# Sheet1_MCU2_0.net
KiCad netlist of a schematic drawn in Altium Designer
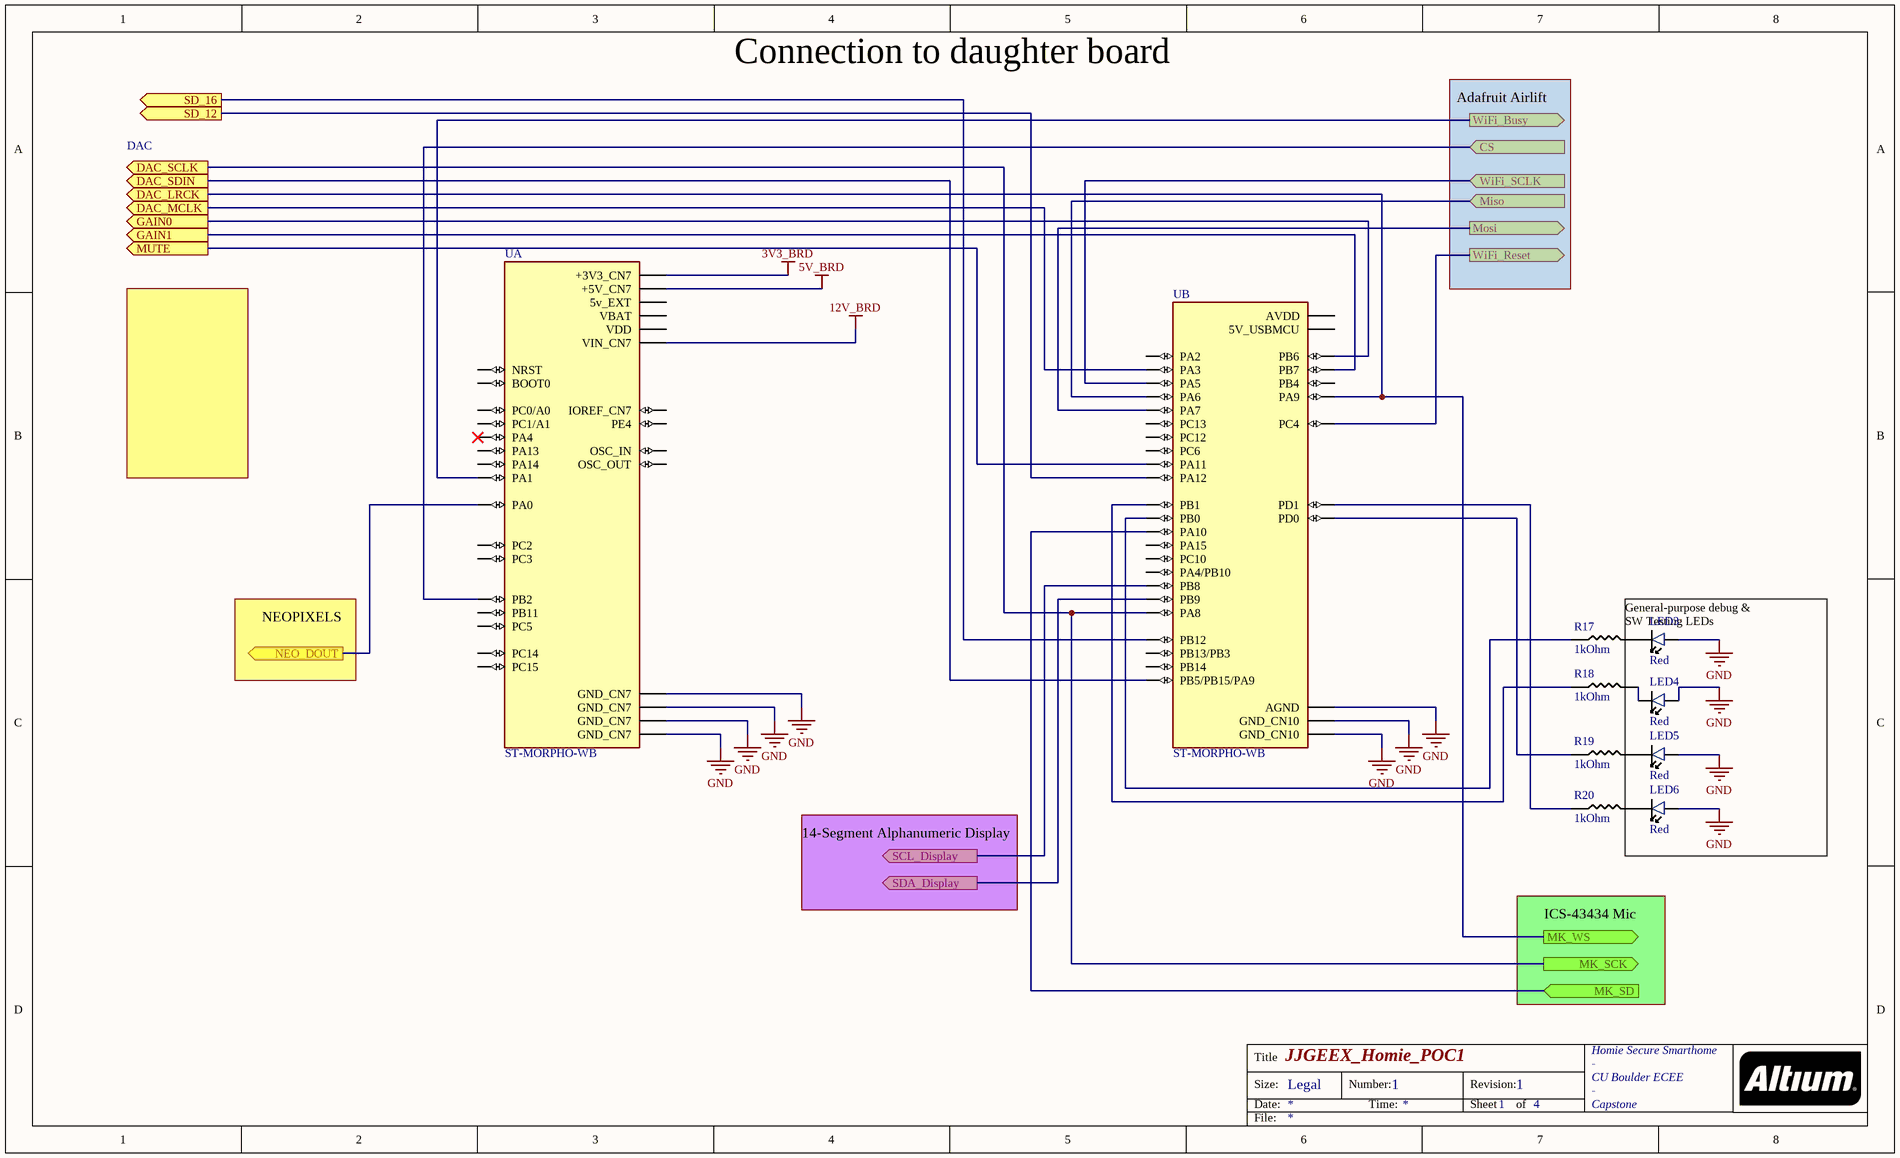
[diagram p0: Sheet1_MCU2.0.SchDoc]

(export (version "E")
  (design (tool "Eeschema 10.0.6"))
  (components
    (comp (ref "LED3")
      (value "Red")
      (footprint "LED0603-R-RD")
      (description "LIGHT EMITTING DIODES (LED) RED 520~625NM 90~100MCD@20MA TOP VIEW 0603 ROHS")
      (fields (field (name "MFR") "Hubei KENTO Elec") (field (name "Comment") "KT-0603R"))
      (libsource (lib "Homie_IntegratedLibraryV2") (part "LED_RED_0603"))
    )
    (comp (ref "LED4")
      (value "Red")
      (footprint "LED0603-R-RD")
      (description "LIGHT EMITTING DIODES (LED) RED 520~625NM 90~100MCD@20MA TOP VIEW 0603 ROHS")
      (fields (field (name "MFR") "Hubei KENTO Elec") (field (name "Comment") "KT-0603R"))
      (libsource (lib "Homie_IntegratedLibraryV2") (part "LED_RED_0603"))
    )
    (comp (ref "LED5")
      (value "Red")
      (footprint "LED0603-R-RD")
      (description "LIGHT EMITTING DIODES (LED) RED 520~625NM 90~100MCD@20MA TOP VIEW 0603 ROHS")
      (fields (field (name "MFR") "Hubei KENTO Elec") (field (name "Comment") "KT-0603R"))
      (libsource (lib "Homie_IntegratedLibraryV2") (part "LED_RED_0603"))
    )
    (comp (ref "LED6")
      (value "Red")
      (footprint "LED0603-R-RD")
      (description "LIGHT EMITTING DIODES (LED) RED 520~625NM 90~100MCD@20MA TOP VIEW 0603 ROHS")
      (fields (field (name "MFR") "Hubei KENTO Elec") (field (name "Comment") "KT-0603R"))
      (libsource (lib "Homie_IntegratedLibraryV2") (part "LED_RED_0603"))
    )
    (comp (ref "R17")
      (value "1kOhm")
      (footprint "R0603")
      (description "1kOhm +-1%  0603")
      (fields (field (name "MFR") "Uniroyal") (field (name "Comment") "1 kOhm"))
      (libsource (lib "Homie_IntegratedLibraryV2") (part "R_1kOhm_0603"))
    )
    (comp (ref "R18")
      (value "1kOhm")
      (footprint "R0603")
      (description "1kOhm +-1%  0603")
      (fields (field (name "MFR") "Uniroyal") (field (name "Comment") "1 kOhm"))
      (libsource (lib "Homie_IntegratedLibraryV2") (part "R_1kOhm_0603"))
    )
    (comp (ref "R19")
      (value "1kOhm")
      (footprint "R0603")
      (description "1kOhm +-1%  0603")
      (fields (field (name "MFR") "Uniroyal") (field (name "Comment") "1 kOhm"))
      (libsource (lib "Homie_IntegratedLibraryV2") (part "R_1kOhm_0603"))
    )
    (comp (ref "R20")
      (value "1kOhm")
      (footprint "R0603")
      (description "1kOhm +-1%  0603")
      (fields (field (name "MFR") "Uniroyal") (field (name "Comment") "1 kOhm"))
      (libsource (lib "Homie_IntegratedLibraryV2") (part "R_1kOhm_0603"))
    )
    (comp (ref "U")
      (value "ST-MORPHO-WB")
      (footprint "ST-MORPHO-WB")
      (description "P-NUCLEO-WB55 Header Footprint")
      (fields (field (name "MF") "STMicroelectronics") (field (name "MP") "NUCLEO-F030R8"))
      (libsource (lib "Homie_IntegratedLibraryV2") (part "ST-MORPHO-WB"))
    )
  )
  (nets
    (net (code "1") (name "/CS") (class "Default")
      (node (ref "U") (pin "CN7_2") (pinfunction "PB2_CN7_2") (pintype "bidirectional"))
    )
    (net (code "2") (name "/DAC_LRCK") (class "Default")
      (node (ref "U") (pin "CN10_19") (pinfunction "PA9_CN10_19") (pintype "bidirectional"))
    )
    (net (code "3") (name "/DAC_MCLK") (class "Default")
      (node (ref "U") (pin "CN10_37") (pinfunction "PA3_CN10_37") (pintype "bidirectional"))
    )
    (net (code "4") (name "/DAC_SCLK") (class "Default")
      (node (ref "U") (pin "CN10_25") (pinfunction "PA8_CN10_25") (pintype "bidirectional"))
    )
    (net (code "5") (name "/DAC_SDIN") (class "Default")
      (node (ref "U") (pin "CN10_26") (pinfunction "PB5/PB15/PA9_CN10_26") (pintype "bidirectional"))
    )
    (net (code "6") (name "/GAIN0") (class "Default")
      (node (ref "U") (pin "CN10_34") (pinfunction "PB6_CN10_34") (pintype "bidirectional"))
    )
    (net (code "7") (name "/GAIN1") (class "Default")
      (node (ref "U") (pin "CN10_6") (pinfunction "PB7_CN10_6") (pintype "bidirectional"))
    )
    (net (code "8") (name "/MK_SD") (class "Default")
      (node (ref "U") (pin "CN10_31") (pinfunction "PA10_CN10_31") (pintype "bidirectional"))
    )
    (net (code "9") (name "/MUTE") (class "Default")
      (node (ref "U") (pin "CN10_14") (pinfunction "PA11_CN10_14") (pintype "bidirectional"))
    )
    (net (code "10") (name "/Miso") (class "Default")
      (node (ref "U") (pin "CN10_13") (pinfunction "PA6_CN10_13") (pintype "bidirectional"))
    )
    (net (code "11") (name "/Mosi") (class "Default")
      (node (ref "U") (pin "CN10_15") (pinfunction "PA7_CN10_15") (pintype "bidirectional"))
    )
    (net (code "12") (name "/NEO_DOUT") (class "Default")
      (node (ref "U") (pin "CN7_34") (pinfunction "PA0_CN7_34") (pintype "bidirectional"))
    )
    (net (code "13") (name "/SCL_Display") (class "Default")
      (node (ref "U") (pin "CN10_3") (pinfunction "PB8_CN10_3") (pintype "bidirectional"))
    )
    (net (code "14") (name "/SDA_Display") (class "Default")
      (node (ref "U") (pin "CN10_5") (pinfunction "PB9_CN10_5") (pintype "bidirectional"))
    )
    (net (code "15") (name "/SD_12") (class "Default")
      (node (ref "U") (pin "CN10_12") (pinfunction "PA12_CN10_12") (pintype "bidirectional"))
    )
    (net (code "16") (name "/SD_16") (class "Default")
      (node (ref "U") (pin "CN10_16") (pinfunction "PB12_CN10_16") (pintype "bidirectional"))
    )
    (net (code "17") (name "/WiFi_Busy") (class "Default")
      (node (ref "U") (pin "CN7_32") (pinfunction "PA1_CN7_32") (pintype "bidirectional"))
    )
    (net (code "18") (name "/WiFi_Reset") (class "Default")
      (node (ref "U") (pin "CN10_1") (pinfunction "PC4_CN10_1") (pintype "bidirectional"))
    )
    (net (code "19") (name "/WiFi_SCLK") (class "Default")
      (node (ref "U") (pin "CN10_11") (pinfunction "PA5_CN10_11") (pintype "bidirectional"))
    )
    (net (code "20") (name "3V3_BRD") (class "Default")
      (node (ref "U") (pin "CN7_16") (pinfunction "+3V3_CN7_CN7_16") (pintype "power_in"))
    )
    (net (code "21") (name "5V_BRD") (class "Default")
      (node (ref "U") (pin "CN7_18") (pinfunction "+5V_CN7_CN7_18") (pintype "power_in"))
    )
    (net (code "22") (name "12V_BRD") (class "Default")
      (node (ref "U") (pin "CN7_24") (pinfunction "VIN_CN7_CN7_24") (pintype "power_in"))
    )
    (net (code "23") (name "GND") (class "Default")
      (node (ref "LED3") (pin "2") (pinfunction "2_2") (pintype "passive"))
      (node (ref "LED4") (pin "2") (pinfunction "2_2") (pintype "passive"))
      (node (ref "LED5") (pin "2") (pinfunction "2_2") (pintype "passive"))
      (node (ref "LED6") (pin "2") (pinfunction "2_2") (pintype "passive"))
      (node (ref "U") (pin "CN10_20") (pinfunction "GND_CN10_CN10_20") (pintype "power_in"))
      (node (ref "U") (pin "CN10_32") (pinfunction "AGND_CN10_32") (pintype "power_in"))
      (node (ref "U") (pin "CN10_9") (pinfunction "GND_CN10_CN10_9") (pintype "power_in"))
      (node (ref "U") (pin "CN7_19") (pinfunction "GND_CN7_CN7_19") (pintype "power_in"))
      (node (ref "U") (pin "CN7_20") (pinfunction "GND_CN7_CN7_20") (pintype "power_in"))
      (node (ref "U") (pin "CN7_22") (pinfunction "GND_CN7_CN7_22") (pintype "power_in"))
      (node (ref "U") (pin "CN7_8") (pinfunction "GND_CN7_CN7_8") (pintype "power_in"))
    )
    (net (code "24") (name "Net-(LED3-Pad1)") (class "Default")
      (node (ref "LED3") (pin "1") (pinfunction "1_1") (pintype "passive"))
      (node (ref "R17") (pin "2") (pinfunction "2_2") (pintype "passive"))
    )
    (net (code "25") (name "Net-(LED4-Pad1)") (class "Default")
      (node (ref "LED4") (pin "1") (pinfunction "1_1") (pintype "passive"))
      (node (ref "R18") (pin "2") (pinfunction "2_2") (pintype "passive"))
    )
    (net (code "26") (name "Net-(LED5-Pad1)") (class "Default")
      (node (ref "LED5") (pin "1") (pinfunction "1_1") (pintype "passive"))
      (node (ref "R19") (pin "2") (pinfunction "2_2") (pintype "passive"))
    )
    (net (code "27") (name "Net-(LED6-Pad1)") (class "Default")
      (node (ref "LED6") (pin "1") (pinfunction "1_1") (pintype "passive"))
      (node (ref "R20") (pin "2") (pinfunction "2_2") (pintype "passive"))
    )
    (net (code "28") (name "Net-(UB-PB0)") (class "Default")
      (node (ref "R17") (pin "1") (pinfunction "1_1") (pintype "passive"))
      (node (ref "U") (pin "CN10_22") (pinfunction "PB0_CN10_22") (pintype "bidirectional"))
    )
    (net (code "29") (name "Net-(UB-PB1)") (class "Default")
      (node (ref "R18") (pin "1") (pinfunction "1_1") (pintype "passive"))
      (node (ref "U") (pin "CN10_24") (pinfunction "PB1_CN10_24") (pintype "bidirectional"))
    )
    (net (code "30") (name "Net-(UB-PD0)") (class "Default")
      (node (ref "R19") (pin "1") (pinfunction "1_1") (pintype "passive"))
      (node (ref "U") (pin "CN10_36") (pinfunction "PD0_CN10_36") (pintype "bidirectional"))
    )
    (net (code "31") (name "Net-(UB-PD1)") (class "Default")
      (node (ref "R20") (pin "1") (pinfunction "1_1") (pintype "passive"))
      (node (ref "U") (pin "CN10_38") (pinfunction "PD1_CN10_38") (pintype "bidirectional"))
    )
    (net (code "32") (name "unconnected-(UA-5v_EXT-PadCN7_6)") (class "Default")
      (node (ref "U") (pin "CN7_6") (pinfunction "5v_EXT_CN7_6") (pintype "power_in"))
    )
    (net (code "33") (name "unconnected-(UA-BOOT0-PadCN7_7)") (class "Default")
      (node (ref "U") (pin "CN7_7") (pinfunction "BOOT0_CN7_7") (pintype "bidirectional"))
    )
    (net (code "34") (name "unconnected-(UA-IOREF_CN7-PadCN7_12)") (class "Default")
      (node (ref "U") (pin "CN7_12") (pinfunction "IOREF_CN7_CN7_12") (pintype "bidirectional"))
    )
    (net (code "35") (name "unconnected-(UA-NRST-PadCN7_14)") (class "Default")
      (node (ref "U") (pin "CN7_14") (pinfunction "NRST_CN7_14") (pintype "bidirectional"))
    )
    (net (code "36") (name "unconnected-(UA-OSC_IN-PadCN7_29)") (class "Default")
      (node (ref "U") (pin "CN7_29") (pinfunction "OSC_IN_CN7_29") (pintype "bidirectional"))
    )
    (net (code "37") (name "unconnected-(UA-OSC_OUT-PadCN7_31)") (class "Default")
      (node (ref "U") (pin "CN7_31") (pinfunction "OSC_OUT_CN7_31") (pintype "bidirectional"))
    )
    (net (code "38") (name "unconnected-(UA-PA4-PadCN7_32)") (class "Default")
      (node (ref "U") (pin "CN7_32") (pinfunction "PA4_CN7_32") (pintype "bidirectional+no_connect"))
    )
    (net (code "39") (name "unconnected-(UA-PA13-PadCN7_13)") (class "Default")
      (node (ref "U") (pin "CN7_13") (pinfunction "PA13_CN7_13") (pintype "bidirectional"))
    )
    (net (code "40") (name "unconnected-(UA-PA14-PadCN7_15)") (class "Default")
      (node (ref "U") (pin "CN7_15") (pinfunction "PA14_CN7_15") (pintype "bidirectional"))
    )
    (net (code "41") (name "unconnected-(UA-PB11-PadCN7_1)") (class "Default")
      (node (ref "U") (pin "CN7_1") (pinfunction "PB11_CN7_1") (pintype "bidirectional"))
    )
    (net (code "42") (name "unconnected-(UA-PC0{slash}A0-PadCN7_28)") (class "Default")
      (node (ref "U") (pin "CN7_28") (pinfunction "PC0/A0_CN7_28") (pintype "bidirectional"))
    )
    (net (code "43") (name "unconnected-(UA-PC1{slash}A1-PadCN7_30)") (class "Default")
      (node (ref "U") (pin "CN7_30") (pinfunction "PC1/A1_CN7_30") (pintype "bidirectional"))
    )
    (net (code "44") (name "unconnected-(UA-PC2-PadCN7_38)") (class "Default")
      (node (ref "U") (pin "CN7_38") (pinfunction "PC2_CN7_38") (pintype "bidirectional"))
    )
    (net (code "45") (name "unconnected-(UA-PC3-PadCN7_36)") (class "Default")
      (node (ref "U") (pin "CN7_36") (pinfunction "PC3_CN7_36") (pintype "bidirectional"))
    )
    (net (code "46") (name "unconnected-(UA-PC5-PadCN7_3)") (class "Default")
      (node (ref "U") (pin "CN7_3") (pinfunction "PC5_CN7_3") (pintype "bidirectional"))
    )
    (net (code "47") (name "unconnected-(UA-PC14-PadCN7_25)") (class "Default")
      (node (ref "U") (pin "CN7_25") (pinfunction "PC14_CN7_25") (pintype "bidirectional"))
    )
    (net (code "48") (name "unconnected-(UA-PC15-PadCN7_27)") (class "Default")
      (node (ref "U") (pin "CN7_27") (pinfunction "PC15_CN7_27") (pintype "bidirectional"))
    )
    (net (code "49") (name "unconnected-(UA-PE4-PadCN7_4)") (class "Default")
      (node (ref "U") (pin "CN7_4") (pinfunction "PE4_CN7_4") (pintype "bidirectional"))
    )
    (net (code "50") (name "unconnected-(UA-VBAT-PadCN7_33)") (class "Default")
      (node (ref "U") (pin "CN7_33") (pinfunction "VBAT_CN7_33") (pintype "power_in"))
    )
    (net (code "51") (name "unconnected-(UA-VDD-PadCN7_5)") (class "Default")
      (node (ref "U") (pin "CN7_5") (pinfunction "VDD_CN7_5") (pintype "power_in"))
    )
    (net (code "52") (name "unconnected-(UB-5V_USBMCU-PadCN10_8)") (class "Default")
      (node (ref "U") (pin "CN10_8") (pinfunction "5V_USBMCU_CN10_8") (pintype "power_in"))
    )
    (net (code "53") (name "unconnected-(UB-AVDD-PadCN10_7)") (class "Default")
      (node (ref "U") (pin "CN10_7") (pinfunction "AVDD_CN10_7") (pintype "power_in"))
    )
    (net (code "54") (name "unconnected-(UB-PA2-PadCN10_35)") (class "Default")
      (node (ref "U") (pin "CN10_35") (pinfunction "PA2_CN10_35") (pintype "bidirectional"))
    )
    (net (code "55") (name "unconnected-(UB-PA4{slash}PB10-PadCN10_17)") (class "Default")
      (node (ref "U") (pin "CN10_17") (pinfunction "PA4/PB10_CN10_17") (pintype "bidirectional"))
    )
    (net (code "56") (name "unconnected-(UB-PA15-PadCN10_27)") (class "Default")
      (node (ref "U") (pin "CN10_27") (pinfunction "PA15_CN10_27") (pintype "bidirectional"))
    )
    (net (code "57") (name "unconnected-(UB-PB4-PadCN10_4)") (class "Default")
      (node (ref "U") (pin "CN10_4") (pinfunction "PB4_CN10_4") (pintype "bidirectional"))
    )
    (net (code "58") (name "unconnected-(UB-PB13{slash}PB3-PadCN10_30)") (class "Default")
      (node (ref "U") (pin "CN10_30") (pinfunction "PB13/PB3_CN10_30") (pintype "bidirectional"))
    )
    (net (code "59") (name "unconnected-(UB-PB14-PadCN10_28)") (class "Default")
      (node (ref "U") (pin "CN10_28") (pinfunction "PB14_CN10_28") (pintype "bidirectional"))
    )
    (net (code "60") (name "unconnected-(UB-PC6-PadCN10_33)") (class "Default")
      (node (ref "U") (pin "CN10_33") (pinfunction "PC6_CN10_33") (pintype "bidirectional"))
    )
    (net (code "61") (name "unconnected-(UB-PC10-PadCN10_29)") (class "Default")
      (node (ref "U") (pin "CN10_29") (pinfunction "PC10_CN10_29") (pintype "bidirectional"))
    )
    (net (code "62") (name "unconnected-(UB-PC12-PadCN10_21)") (class "Default")
      (node (ref "U") (pin "CN10_21") (pinfunction "PC12_CN10_21") (pintype "bidirectional"))
    )
    (net (code "63") (name "unconnected-(UB-PC13-PadCN10_23)") (class "Default")
      (node (ref "U") (pin "CN10_23") (pinfunction "PC13_CN10_23") (pintype "bidirectional"))
    )
  )
)
